# CAN-to-CAN.net
KiCad netlist of a schematic drawn in Altium Designer
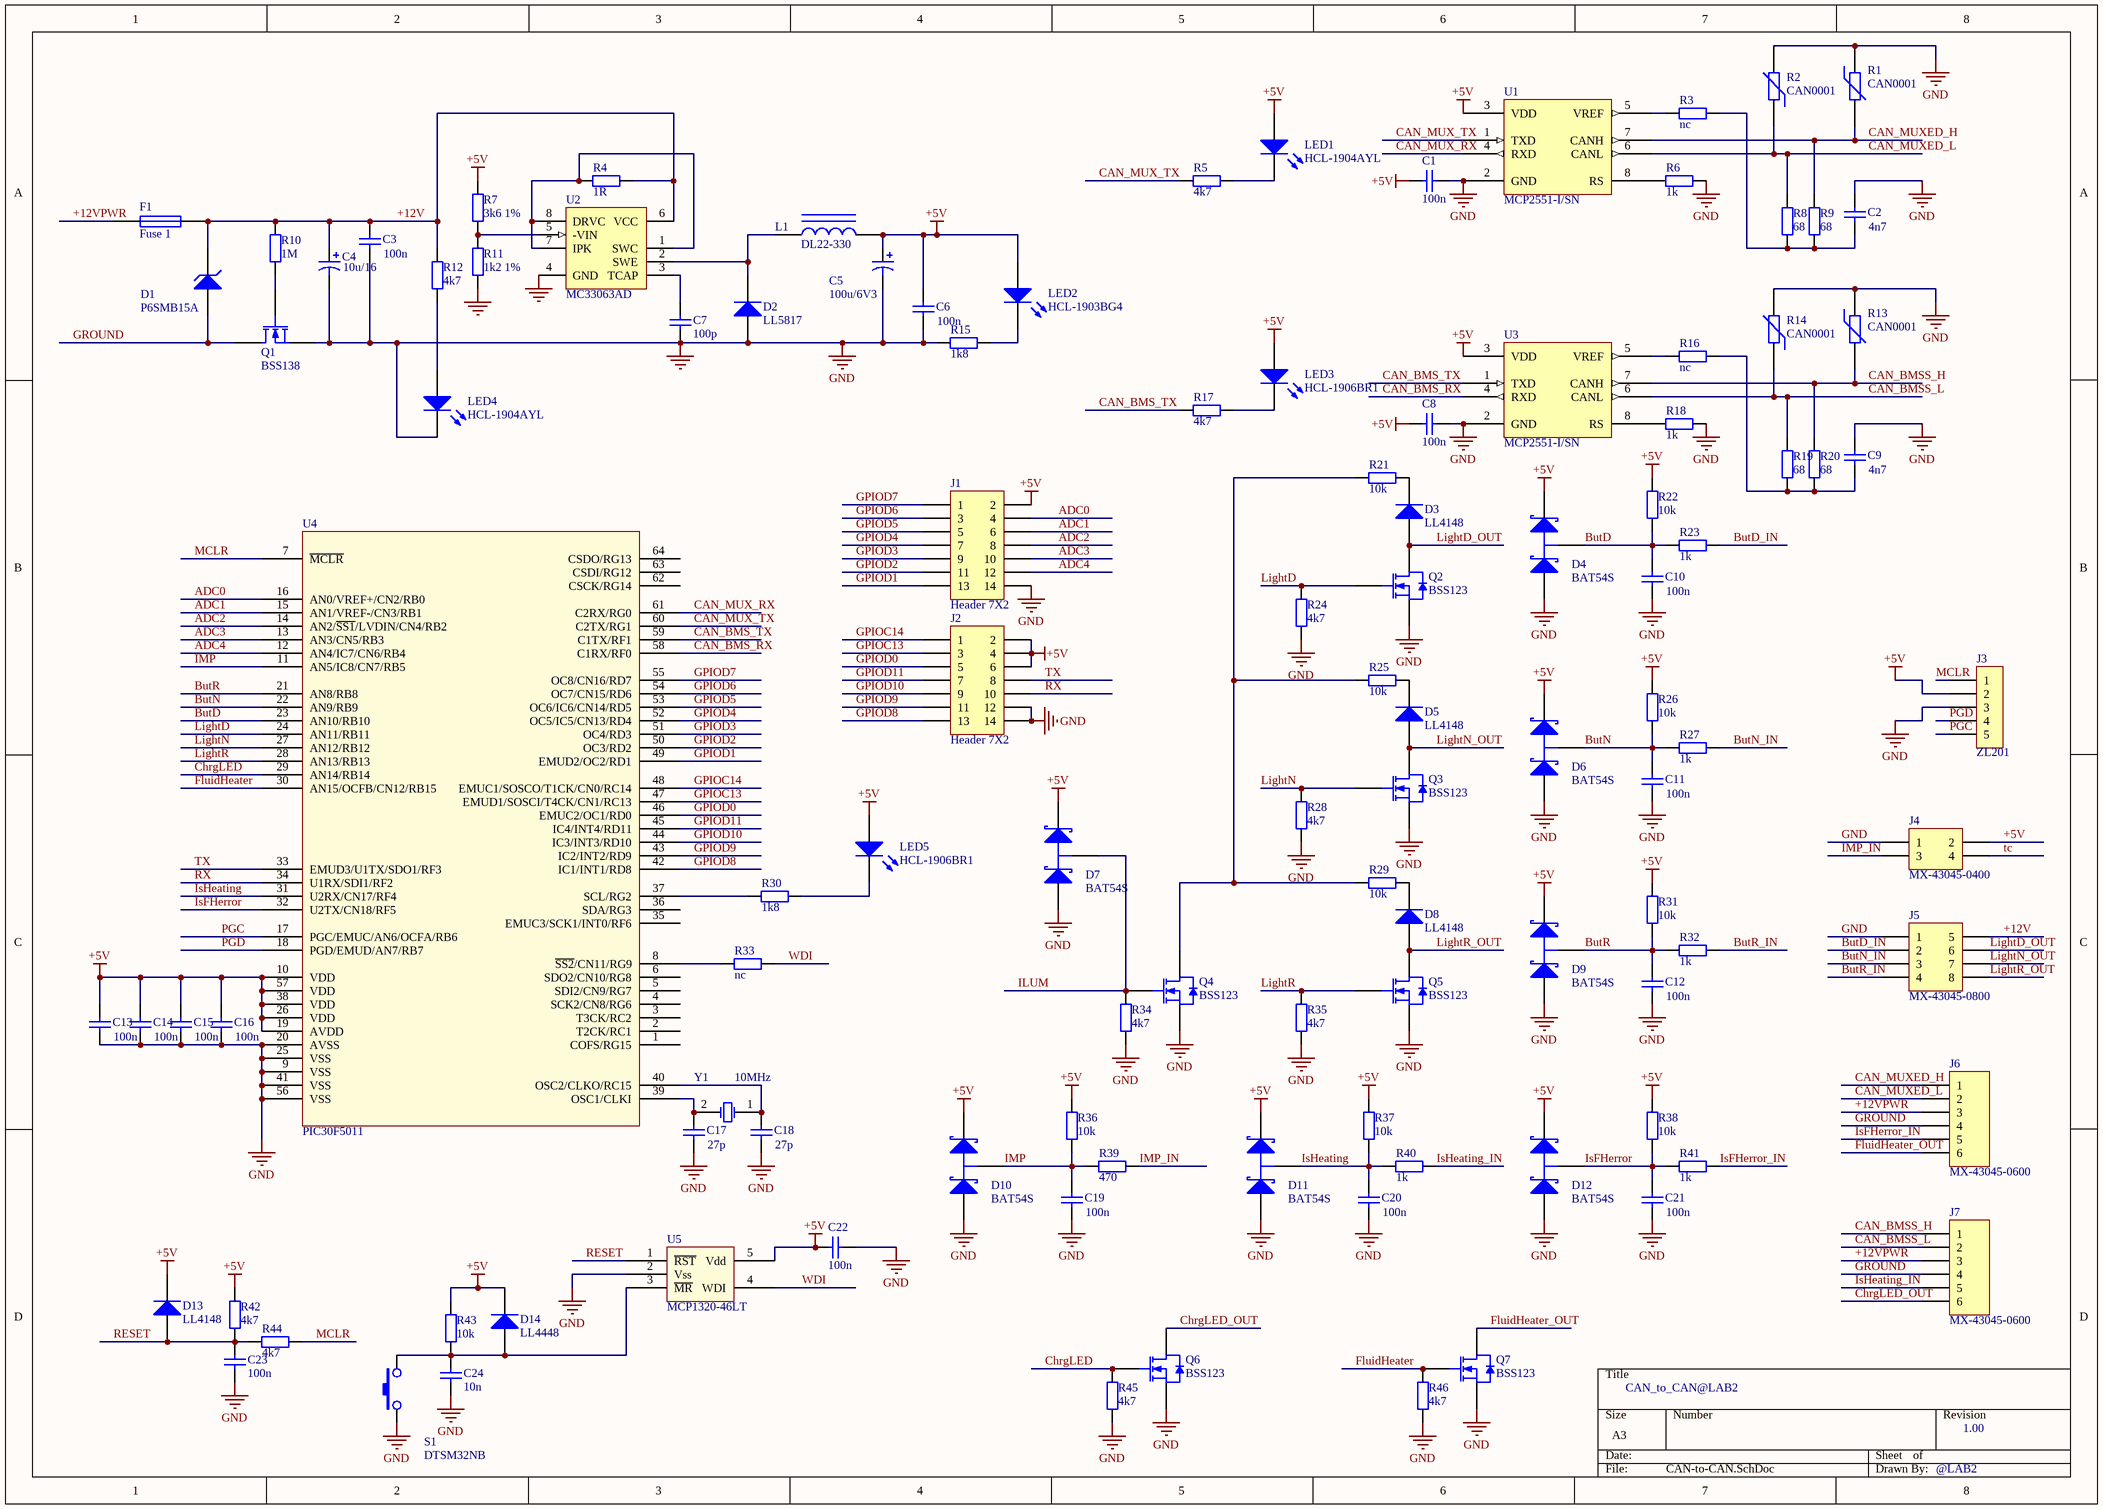
[diagram p0: CAN-to-CAN.SchDoc]

(export (version "E")
  (design (tool "Eeschema 10.0.6"))
  (components
    (comp (ref "C1")
      (value "100n")
      (footprint "0603")
      (description "Capacitor")
      (libsource (lib "Miscellaneous Devices") (part "Cap"))
    )
    (comp (ref "C2")
      (value "4n7")
      (footprint "0603")
      (description "Capacitor")
      (libsource (lib "Miscellaneous Devices") (part "Cap"))
    )
    (comp (ref "C3")
      (value "100n")
      (footprint "3.2X1.6X1.1")
      (description "Capacitor")
      (libsource (lib "Miscellaneous Devices") (part "Cap"))
    )
    (comp (ref "C4")
      (value "10u/16")
      (footprint "1608[0603]")
      (description "Polarized Capacitor (Radial)")
      (libsource (lib "Miscellaneous Devices") (part "Cap Pol1"))
    )
    (comp (ref "C5")
      (value "100u/6V3")
      (footprint "0402")
      (description "Polarized Capacitor (Radial)")
      (libsource (lib "Miscellaneous Devices") (part "Cap Pol1"))
    )
    (comp (ref "C6")
      (value "100n")
      (footprint "0603")
      (description "Capacitor")
      (libsource (lib "Miscellaneous Devices") (part "Cap"))
    )
    (comp (ref "C7")
      (value "100p")
      (footprint "0603")
      (description "Capacitor")
      (libsource (lib "Miscellaneous Devices") (part "Cap"))
    )
    (comp (ref "C8")
      (value "100n")
      (footprint "0603")
      (description "Capacitor")
      (libsource (lib "Miscellaneous Devices") (part "Cap"))
    )
    (comp (ref "C9")
      (value "4n7")
      (footprint "0603")
      (description "Capacitor")
      (libsource (lib "Miscellaneous Devices") (part "Cap"))
    )
    (comp (ref "C10")
      (value "100n")
      (footprint "0603")
      (description "Capacitor")
      (libsource (lib "Miscellaneous Devices") (part "Cap"))
    )
    (comp (ref "C11")
      (value "100n")
      (footprint "0603")
      (description "Capacitor")
      (libsource (lib "Miscellaneous Devices") (part "Cap"))
    )
    (comp (ref "C12")
      (value "100n")
      (footprint "0603")
      (description "Capacitor")
      (libsource (lib "Miscellaneous Devices") (part "Cap"))
    )
    (comp (ref "C13")
      (value "100n")
      (footprint "0603")
      (description "Capacitor")
      (libsource (lib "Miscellaneous Devices") (part "Cap"))
    )
    (comp (ref "C14")
      (value "100n")
      (footprint "0603")
      (description "Capacitor")
      (libsource (lib "Miscellaneous Devices") (part "Cap"))
    )
    (comp (ref "C15")
      (value "100n")
      (footprint "0603")
      (description "Capacitor")
      (libsource (lib "Miscellaneous Devices") (part "Cap"))
    )
    (comp (ref "C16")
      (value "100n")
      (footprint "0603")
      (description "Capacitor")
      (libsource (lib "Miscellaneous Devices") (part "Cap"))
    )
    (comp (ref "C17")
      (value "27p")
      (footprint "0603")
      (description "Capacitor")
      (libsource (lib "Miscellaneous Devices") (part "Cap"))
    )
    (comp (ref "C18")
      (value "27p")
      (footprint "0603")
      (description "Capacitor")
      (libsource (lib "Miscellaneous Devices") (part "Cap"))
    )
    (comp (ref "C19")
      (value "100n")
      (footprint "0603")
      (description "Capacitor")
      (libsource (lib "Miscellaneous Devices") (part "Cap"))
    )
    (comp (ref "C20")
      (value "100n")
      (footprint "0603")
      (description "Capacitor")
      (libsource (lib "Miscellaneous Devices") (part "Cap"))
    )
    (comp (ref "C21")
      (value "100n")
      (footprint "0603")
      (description "Capacitor")
      (libsource (lib "Miscellaneous Devices") (part "Cap"))
    )
    (comp (ref "C22")
      (value "100n")
      (footprint "0603")
      (description "Capacitor")
      (libsource (lib "Miscellaneous Devices") (part "Cap"))
    )
    (comp (ref "C23")
      (value "100n")
      (footprint "0603")
      (description "Capacitor")
      (libsource (lib "Miscellaneous Devices") (part "Cap"))
    )
    (comp (ref "C24")
      (value "10n")
      (footprint "0603")
      (description "Capacitor")
      (libsource (lib "Miscellaneous Devices") (part "Cap"))
    )
    (comp (ref "D1")
      (value "P6SMB15A")
      (footprint "SMB")
      (description "Zener Diode")
      (libsource (lib "Miscellaneous Devices") (part "D Zener"))
    )
    (comp (ref "D2")
      (value "LL5817")
      (footprint "3.2X1.6X1.1")
      (description "High Conductance Fast Diode")
      (libsource (lib "FSC Discrete Diode") (part "1N4148"))
    )
    (comp (ref "D3")
      (value "LL4148")
      (footprint "3.2X1.6X1.1")
      (description "High Conductance Fast Diode")
      (libsource (lib "FSC Discrete Diode") (part "1N4148"))
    )
    (comp (ref "D4")
      (value "BAT54S")
      (footprint "3.2X1.6X1.1")
      (description "Schottky Barrier Double Diode")
      (libsource (lib "Philips Discrete Diode - Schottky") (part "BAT54S"))
    )
    (comp (ref "D5")
      (value "LL4148")
      (footprint "3.2X1.6X1.1")
      (description "High Conductance Fast Diode")
      (libsource (lib "FSC Discrete Diode") (part "1N4148"))
    )
    (comp (ref "D6")
      (value "BAT54S")
      (footprint "3.5X2.8X1.9")
      (description "Schottky Barrier Double Diode")
      (libsource (lib "Philips Discrete Diode - Schottky") (part "BAT54S"))
    )
    (comp (ref "D7")
      (value "BAT54S")
      (footprint "3.2X1.6X1.1")
      (description "Schottky Barrier Double Diode")
      (libsource (lib "Philips Discrete Diode - Schottky") (part "BAT54S"))
    )
    (comp (ref "D8")
      (value "LL4148")
      (footprint "3.2X1.6X1.1")
      (description "High Conductance Fast Diode")
      (libsource (lib "FSC Discrete Diode") (part "1N4148"))
    )
    (comp (ref "D9")
      (value "BAT54S")
      (footprint "3.5X2.8X1.9")
      (description "Schottky Barrier Double Diode")
      (libsource (lib "Philips Discrete Diode - Schottky") (part "BAT54S"))
    )
    (comp (ref "D10")
      (value "BAT54S")
      (footprint "3.2X1.6X1.1")
      (description "Schottky Barrier Double Diode")
      (libsource (lib "Philips Discrete Diode - Schottky") (part "BAT54S"))
    )
    (comp (ref "D11")
      (value "BAT54S")
      (footprint "3.2X1.6X1.1")
      (description "Schottky Barrier Double Diode")
      (libsource (lib "Philips Discrete Diode - Schottky") (part "BAT54S"))
    )
    (comp (ref "D12")
      (value "BAT54S")
      (footprint "3.2X1.6X1.1")
      (description "Schottky Barrier Double Diode")
      (libsource (lib "Philips Discrete Diode - Schottky") (part "BAT54S"))
    )
    (comp (ref "D13")
      (value "LL4148")
      (footprint "3.2X1.6X1.1")
      (description "High Conductance Fast Diode")
      (libsource (lib "FSC Discrete Diode") (part "1N4148"))
    )
    (comp (ref "D14")
      (value "LL4448")
      (footprint "3.2X1.6X1.1")
      (description "Default Diode")
      (libsource (lib "Miscellaneous Devices") (part "Diode"))
    )
    (comp (ref "F1")
      (value "Fuse 1")
      (footprint "1812")
      (description "Fuse")
      (libsource (lib "Miscellaneous Devices") (part "Fuse 1"))
    )
    (comp (ref "J1")
      (value "Header 7X2")
      (footprint "HDR2X7")
      (description "Header, 7-Pin, Dual row")
      (libsource (lib "Miscellaneous Connectors") (part "Header 7X2"))
    )
    (comp (ref "J2")
      (value "Header 7X2")
      (footprint "HDR2X7")
      (description "Header, 7-Pin, Dual row")
      (libsource (lib "Miscellaneous Connectors") (part "Header 7X2"))
    )
    (comp (ref "J3")
      (value "ZL201")
      (footprint "HDR1X5")
      (description "Connector")
      (libsource (lib "*") (part "CON5"))
    )
    (comp (ref "J4")
      (value "MX-43045-0400")
      (footprint "MHDR2X2")
      (description "Header, 2-Pin, Dual row")
      (libsource (lib "Miscellaneous Connectors") (part "Header 2X2"))
    )
    (comp (ref "J5")
      (value "MX-43045-0800")
      (footprint "MHDR2X8")
      (description "Header, 4-Pin, Dual row")
      (libsource (lib "Miscellaneous Connectors") (part "Header 4X2A"))
    )
    (comp (ref "J6")
      (value "MX-43045-0600")
      (footprint "MHDR1X6")
      (description "Header, 6-Pin")
      (libsource (lib "Miscellaneous Connectors") (part "Header 6"))
    )
    (comp (ref "J7")
      (value "MX-43045-0600")
      (footprint "MHDR1X6")
      (description "Header, 6-Pin")
      (libsource (lib "Miscellaneous Connectors") (part "Header 6"))
    )
    (comp (ref "L1")
      (value "DL22-330")
      (footprint "14-1210")
      (description "Magnetic-Core Inductor")
      (libsource (lib "Miscellaneous Devices") (part "Inductor Iron"))
    )
    (comp (ref "LED1")
      (value "HCL-1904AYL")
      (footprint "0603")
      (description "Typical BLUE SiC LED")
      (libsource (lib "Miscellaneous Devices") (part "LED3"))
    )
    (comp (ref "LED2")
      (value "HCL-1903BG4")
      (footprint "0603")
      (description "Typical BLUE SiC LED")
      (libsource (lib "Miscellaneous Devices") (part "LED3"))
    )
    (comp (ref "LED3")
      (value "HCL-1906BR1")
      (footprint "0603")
      (description "Typical BLUE SiC LED")
      (libsource (lib "Miscellaneous Devices") (part "LED3"))
    )
    (comp (ref "LED4")
      (value "HCL-1904AYL")
      (footprint "0603")
      (description "Typical BLUE SiC LED")
      (libsource (lib "Miscellaneous Devices") (part "LED3"))
    )
    (comp (ref "LED5")
      (value "HCL-1906BR1")
      (footprint "0603")
      (description "Typical BLUE SiC LED")
      (libsource (lib "Miscellaneous Devices") (part "LED3"))
    )
    (comp (ref "Q1")
      (value "BSS138")
      (footprint "3.2X1.6X1.1")
      (description "N-Channel Enhancement Mode Vertical DMOS FET")
      (libsource (lib "Zetex Discrete MOSFET") (part "BSS138"))
    )
    (comp (ref "Q2")
      (value "BSS123")
      (footprint "3.2X1.6X1.1")
      (description "N-channel Enhancement Mode Vertical D-MOSFET")
      (libsource (lib "Philips Discrete MOSFET - Low Power") (part "BSS123"))
    )
    (comp (ref "Q3")
      (value "BSS123")
      (footprint "3.2X1.6X1.1")
      (description "N-channel Enhancement Mode Vertical D-MOSFET")
      (libsource (lib "Philips Discrete MOSFET - Low Power") (part "BSS123"))
    )
    (comp (ref "Q4")
      (value "BSS123")
      (footprint "3.5X2.8X1.9")
      (description "N-channel Enhancement Mode Vertical D-MOSFET")
      (libsource (lib "Philips Discrete MOSFET - Low Power") (part "BSS123"))
    )
    (comp (ref "Q5")
      (value "BSS123")
      (footprint "3.5X2.8X1.9")
      (description "N-channel Enhancement Mode Vertical D-MOSFET")
      (libsource (lib "Philips Discrete MOSFET - Low Power") (part "BSS123"))
    )
    (comp (ref "Q6")
      (value "BSS123")
      (footprint "3.2X1.6X1.1")
      (description "N-channel Enhancement Mode Vertical D-MOSFET")
      (libsource (lib "Philips Discrete MOSFET - Low Power") (part "BSS123"))
    )
    (comp (ref "Q7")
      (value "BSS123")
      (footprint "3.5X2.8X1.9")
      (description "N-channel Enhancement Mode Vertical D-MOSFET")
      (libsource (lib "Philips Discrete MOSFET - Low Power") (part "BSS123"))
    )
    (comp (ref "R1")
      (value "CAN0001")
      (footprint "0603")
      (description "Varistor (Voltage-Sensitive Resistor)")
      (libsource (lib "Miscellaneous Devices") (part "Res Varistor"))
    )
    (comp (ref "R2")
      (value "CAN0001")
      (footprint "0603")
      (description "Varistor (Voltage-Sensitive Resistor)")
      (libsource (lib "Miscellaneous Devices") (part "Res Varistor"))
    )
    (comp (ref "R3")
      (value "nc")
      (footprint "0603")
      (description "Resistor")
      (libsource (lib "") (part "Res2_1"))
    )
    (comp (ref "R4")
      (value "1R")
      (footprint "RESC6332")
      (description "Resistor")
      (libsource (lib "") (part "Res2_1"))
    )
    (comp (ref "R5")
      (value "4k7")
      (footprint "0603")
      (description "Resistor")
      (libsource (lib "") (part "Res2_2"))
    )
    (comp (ref "R6")
      (value "1k")
      (footprint "0603")
      (description "Resistor")
      (libsource (lib "") (part "Res2_1"))
    )
    (comp (ref "R7")
      (value "3k6 1%")
      (footprint "0603")
      (description "Resistor")
      (libsource (lib "Miscellaneous Devices") (part "Res2"))
    )
    (comp (ref "R8")
      (value "68")
      (footprint "0603")
      (description "Resistor")
      (libsource (lib "Miscellaneous Devices") (part "Res2"))
    )
    (comp (ref "R9")
      (value "68")
      (footprint "0603")
      (description "Resistor")
      (libsource (lib "Miscellaneous Devices") (part "Res2"))
    )
    (comp (ref "R10")
      (value "1M")
      (footprint "0603")
      (description "Resistor")
      (libsource (lib "Miscellaneous Devices") (part "Res2"))
    )
    (comp (ref "R11")
      (value "1k2 1%")
      (footprint "0603")
      (description "Resistor")
      (libsource (lib "") (part "Res2_3"))
    )
    (comp (ref "R12")
      (value "4k7")
      (footprint "0603")
      (description "Resistor")
      (libsource (lib "Miscellaneous Devices") (part "Res2"))
    )
    (comp (ref "R13")
      (value "CAN0001")
      (footprint "0603")
      (description "Varistor (Voltage-Sensitive Resistor)")
      (libsource (lib "Miscellaneous Devices") (part "Res Varistor"))
    )
    (comp (ref "R14")
      (value "CAN0001")
      (footprint "0603")
      (description "Varistor (Voltage-Sensitive Resistor)")
      (libsource (lib "Miscellaneous Devices") (part "Res Varistor"))
    )
    (comp (ref "R15")
      (value "1k8")
      (footprint "0603")
      (description "Resistor")
      (libsource (lib "") (part "Res2_2"))
    )
    (comp (ref "R16")
      (value "nc")
      (footprint "0603")
      (description "Resistor")
      (libsource (lib "") (part "Res2_1"))
    )
    (comp (ref "R17")
      (value "4k7")
      (footprint "0603")
      (description "Resistor")
      (libsource (lib "") (part "Res2_2"))
    )
    (comp (ref "R18")
      (value "1k")
      (footprint "0603")
      (description "Resistor")
      (libsource (lib "") (part "Res2_1"))
    )
    (comp (ref "R19")
      (value "68")
      (footprint "0603")
      (description "Resistor")
      (libsource (lib "Miscellaneous Devices") (part "Res2"))
    )
    (comp (ref "R20")
      (value "68")
      (footprint "0603")
      (description "Resistor")
      (libsource (lib "Miscellaneous Devices") (part "Res2"))
    )
    (comp (ref "R21")
      (value "10k")
      (footprint "0603")
      (description "Resistor")
      (libsource (lib "") (part "Res2_1"))
    )
    (comp (ref "R22")
      (value "10k")
      (footprint "0603")
      (description "Resistor")
      (libsource (lib "Miscellaneous Devices") (part "Res2"))
    )
    (comp (ref "R23")
      (value "1k")
      (footprint "0603")
      (description "Resistor")
      (libsource (lib "") (part "Res2_2"))
    )
    (comp (ref "R24")
      (value "4k7")
      (footprint "0603")
      (description "Resistor")
      (libsource (lib "Miscellaneous Devices") (part "Res2"))
    )
    (comp (ref "R25")
      (value "10k")
      (footprint "0603")
      (description "Resistor")
      (libsource (lib "") (part "Res2_1"))
    )
    (comp (ref "R26")
      (value "10k")
      (footprint "0603")
      (description "Resistor")
      (libsource (lib "Miscellaneous Devices") (part "Res2"))
    )
    (comp (ref "R27")
      (value "1k")
      (footprint "0603")
      (description "Resistor")
      (libsource (lib "") (part "Res2_2"))
    )
    (comp (ref "R28")
      (value "4k7")
      (footprint "0603")
      (description "Resistor")
      (libsource (lib "Miscellaneous Devices") (part "Res2"))
    )
    (comp (ref "R29")
      (value "10k")
      (footprint "0603")
      (description "Resistor")
      (libsource (lib "") (part "Res2_1"))
    )
    (comp (ref "R30")
      (value "1k8")
      (footprint "0603")
      (description "Resistor")
      (libsource (lib "") (part "Res2_2"))
    )
    (comp (ref "R31")
      (value "10k")
      (footprint "0603")
      (description "Resistor")
      (libsource (lib "Miscellaneous Devices") (part "Res2"))
    )
    (comp (ref "R32")
      (value "1k")
      (footprint "0603")
      (description "Resistor")
      (libsource (lib "") (part "Res2_2"))
    )
    (comp (ref "R33")
      (value "nc")
      (footprint "0603")
      (description "Resistor")
      (libsource (lib "") (part "Res2_2"))
    )
    (comp (ref "R34")
      (value "4k7")
      (footprint "0603")
      (description "Resistor")
      (libsource (lib "Miscellaneous Devices") (part "Res2"))
    )
    (comp (ref "R35")
      (value "4k7")
      (footprint "0603")
      (description "Resistor")
      (libsource (lib "Miscellaneous Devices") (part "Res2"))
    )
    (comp (ref "R36")
      (value "10k")
      (footprint "0603")
      (description "Resistor")
      (libsource (lib "Miscellaneous Devices") (part "Res2"))
    )
    (comp (ref "R37")
      (value "10k")
      (footprint "0603")
      (description "Resistor")
      (libsource (lib "Miscellaneous Devices") (part "Res2"))
    )
    (comp (ref "R38")
      (value "10k")
      (footprint "0603")
      (description "Resistor")
      (libsource (lib "Miscellaneous Devices") (part "Res2"))
    )
    (comp (ref "R39")
      (value "470")
      (footprint "0603")
      (description "Resistor")
      (libsource (lib "") (part "Res2_2"))
    )
    (comp (ref "R40")
      (value "1k")
      (footprint "0603")
      (description "Resistor")
      (libsource (lib "") (part "Res2_2"))
    )
    (comp (ref "R41")
      (value "1k")
      (footprint "0603")
      (description "Resistor")
      (libsource (lib "") (part "Res2_2"))
    )
    (comp (ref "R42")
      (value "4k7")
      (footprint "0603")
      (description "Resistor")
      (libsource (lib "Miscellaneous Devices") (part "Res2"))
    )
    (comp (ref "R43")
      (value "10k")
      (footprint "0603")
      (description "Resistor")
      (libsource (lib "") (part "Res2_3"))
    )
    (comp (ref "R44")
      (value "4k7")
      (footprint "0603")
      (description "Resistor")
      (libsource (lib "") (part "Res2_2"))
    )
    (comp (ref "R45")
      (value "4k7")
      (footprint "0603")
      (description "Resistor")
      (libsource (lib "Miscellaneous Devices") (part "Res2"))
    )
    (comp (ref "R46")
      (value "4k7")
      (footprint "0603")
      (description "Resistor")
      (libsource (lib "Miscellaneous Devices") (part "Res2"))
    )
    (comp (ref "S1")
      (value "DTSM32NB")
      (footprint "3.5X2.8X1.9")
      (description "Switch PushButton")
      (libsource (lib "*") (part "PUSHB"))
    )
    (comp (ref "U1")
      (value "MCP2551-I/SN")
      (footprint "HDR2X8")
      (description "High Speed CAN Transceiver, 8-Pin Plastic SOIC, Industrial Grade")
      (libsource (lib "Microchip Interface Line Transceiver") (part "MCP2551-I/SN"))
    )
    (comp (ref "U2")
      (value "MC33063AD")
      (footprint "SO8_N")
      (description "DC-to-DC Converter Control Circuit")
      (libsource (lib "Motorola Power Mgt DC-DC Converter") (part "MC33063AD"))
    )
    (comp (ref "U3")
      (value "MCP2551-I/SN")
      (footprint "MHDR1X8")
      (description "High Speed CAN Transceiver, 8-Pin Plastic SOIC, Industrial Grade")
      (libsource (lib "Microchip Interface Line Transceiver") (part "MCP2551-I/SN"))
    )
    (comp (ref "U4")
      (value "PIC30F5011")
      (footprint "QFP50P1200X1200X120-64N")
      (description "PIC30F5011 - Up")
      (libsource (lib "X-Tro's Misc") (part "PIC30F5011"))
    )
    (comp (ref "U5")
      (value "MCP1320-46LT")
      (footprint "HDR1X5")
      (libsource (lib "X-Tro's Misc") (part "MCP1320"))
    )
    (comp (ref "Y1")
      (value "10MHz")
      (footprint "3.2X1.6X1.1")
      (description "Crystal Oscillator")
      (libsource (lib "Miscellaneous Devices") (part "XTAL"))
    )
  )
  (nets
    (net (code "1") (name "+5V") (class "Default")
      (node (ref "C1") (pin "1") (pinfunction "1_1") (pintype "passive"))
      (node (ref "C13") (pin "1") (pinfunction "1_1") (pintype "passive"))
      (node (ref "C14") (pin "1") (pinfunction "1_1") (pintype "passive"))
      (node (ref "C15") (pin "1") (pinfunction "1_1") (pintype "passive"))
      (node (ref "C16") (pin "1") (pinfunction "1_1") (pintype "passive"))
      (node (ref "C22") (pin "1") (pinfunction "1_1") (pintype "passive"))
      (node (ref "C5") (pin "1") (pinfunction "1_1") (pintype "passive"))
      (node (ref "C6") (pin "1") (pinfunction "1_1") (pintype "passive"))
      (node (ref "C8") (pin "1") (pinfunction "1_1") (pintype "passive"))
      (node (ref "D10") (pin "2") (pinfunction "K_2") (pintype "passive"))
      (node (ref "D11") (pin "2") (pinfunction "K_2") (pintype "passive"))
      (node (ref "D12") (pin "2") (pinfunction "K_2") (pintype "passive"))
      (node (ref "D13") (pin "2") (pinfunction "K_2") (pintype "passive"))
      (node (ref "D14") (pin "2") (pinfunction "K_2") (pintype "passive"))
      (node (ref "D4") (pin "2") (pinfunction "K_2") (pintype "passive"))
      (node (ref "D6") (pin "2") (pinfunction "K_2") (pintype "passive"))
      (node (ref "D7") (pin "2") (pinfunction "K_2") (pintype "passive"))
      (node (ref "D9") (pin "2") (pinfunction "K_2") (pintype "passive"))
      (node (ref "J1") (pin "2") (pinfunction "2_2") (pintype "passive"))
      (node (ref "J2") (pin "2") (pinfunction "2_2") (pintype "passive"))
      (node (ref "J2") (pin "4") (pinfunction "4_4") (pintype "passive"))
      (node (ref "J2") (pin "6") (pinfunction "6_6") (pintype "passive"))
      (node (ref "J3") (pin "2") (pinfunction "2_2") (pintype "passive"))
      (node (ref "J4") (pin "2") (pinfunction "2_2") (pintype "passive"))
      (node (ref "L1") (pin "2") (pinfunction "2_2") (pintype "passive"))
      (node (ref "LED1") (pin "1") (pinfunction "A_1") (pintype "passive"))
      (node (ref "LED2") (pin "1") (pinfunction "A_1") (pintype "passive"))
      (node (ref "LED3") (pin "1") (pinfunction "A_1") (pintype "passive"))
      (node (ref "LED5") (pin "1") (pinfunction "A_1") (pintype "passive"))
      (node (ref "R22") (pin "1") (pinfunction "1_1") (pintype "passive"))
      (node (ref "R26") (pin "1") (pinfunction "1_1") (pintype "passive"))
      (node (ref "R31") (pin "1") (pinfunction "1_1") (pintype "passive"))
      (node (ref "R36") (pin "1") (pinfunction "1_1") (pintype "passive"))
      (node (ref "R37") (pin "1") (pinfunction "1_1") (pintype "passive"))
      (node (ref "R38") (pin "1") (pinfunction "1_1") (pintype "passive"))
      (node (ref "R42") (pin "1") (pinfunction "1_1") (pintype "passive"))
      (node (ref "R43") (pin "2") (pinfunction "2_2") (pintype "passive"))
      (node (ref "R7") (pin "1") (pinfunction "1_1") (pintype "passive"))
      (node (ref "U1") (pin "3") (pinfunction "VDD_3") (pintype "power_in"))
      (node (ref "U3") (pin "3") (pinfunction "VDD_3") (pintype "power_in"))
      (node (ref "U4") (pin "10") (pinfunction "VDD_10") (pintype "passive"))
      (node (ref "U4") (pin "19") (pinfunction "AVDD_19") (pintype "passive"))
      (node (ref "U4") (pin "26") (pinfunction "VDD_26") (pintype "passive"))
      (node (ref "U4") (pin "38") (pinfunction "VDD_38") (pintype "passive"))
      (node (ref "U4") (pin "57") (pinfunction "VDD_57") (pintype "passive"))
      (node (ref "U5") (pin "5") (pinfunction "Vdd_5") (pintype "passive"))
    )
    (net (code "2") (name "/+12V") (class "Default")
      (node (ref "C3") (pin "1") (pinfunction "1_1") (pintype "passive"))
      (node (ref "C4") (pin "1") (pinfunction "1_1") (pintype "passive"))
      (node (ref "D1") (pin "2") (pinfunction "K_2") (pintype "passive"))
      (node (ref "F1") (pin "2") (pinfunction "2_2") (pintype "passive"))
      (node (ref "J5") (pin "5") (pinfunction "5_5") (pintype "passive"))
      (node (ref "R10") (pin "1") (pinfunction "1_1") (pintype "passive"))
      (node (ref "R12") (pin "1") (pinfunction "1_1") (pintype "passive"))
      (node (ref "R4") (pin "2") (pinfunction "2_2") (pintype "passive"))
      (node (ref "U2") (pin "6") (pinfunction "VCC_6") (pintype "power_in"))
    )
    (net (code "3") (name "/+12VPWR") (class "Default")
      (node (ref "F1") (pin "1") (pinfunction "1_1") (pintype "passive"))
      (node (ref "J6") (pin "3") (pinfunction "3_3") (pintype "passive"))
      (node (ref "J7") (pin "3") (pinfunction "3_3") (pintype "passive"))
    )
    (net (code "4") (name "/ADC0") (class "Default")
      (node (ref "J1") (pin "4") (pinfunction "4_4") (pintype "passive"))
      (node (ref "U4") (pin "16") (pinfunction "AN0/VREF+/CN2/RB0_16") (pintype "passive"))
    )
    (net (code "5") (name "/ADC1") (class "Default")
      (node (ref "J1") (pin "6") (pinfunction "6_6") (pintype "passive"))
      (node (ref "U4") (pin "15") (pinfunction "AN1/VREF-/CN3/RB1_15") (pintype "passive"))
    )
    (net (code "6") (name "/ADC2") (class "Default")
      (node (ref "J1") (pin "8") (pinfunction "8_8") (pintype "passive"))
      (node (ref "U4") (pin "14") (pinfunction "AN2/~{SS1}/LVDIN/CN4/RB2_14") (pintype "passive"))
    )
    (net (code "7") (name "/ADC3") (class "Default")
      (node (ref "J1") (pin "10") (pinfunction "10_10") (pintype "passive"))
      (node (ref "U4") (pin "13") (pinfunction "AN3/CN5/RB3_13") (pintype "passive"))
    )
    (net (code "8") (name "/ADC4") (class "Default")
      (node (ref "J1") (pin "12") (pinfunction "12_12") (pintype "passive"))
      (node (ref "U4") (pin "12") (pinfunction "AN4/IC7/CN6/RB4_12") (pintype "passive"))
    )
    (net (code "9") (name "/ButD") (class "Default")
      (node (ref "C10") (pin "1") (pinfunction "1_1") (pintype "passive"))
      (node (ref "D4") (pin "3") (pinfunction "C_3") (pintype "passive"))
      (node (ref "R22") (pin "2") (pinfunction "2_2") (pintype "passive"))
      (node (ref "R23") (pin "2") (pinfunction "2_2") (pintype "passive"))
      (node (ref "U4") (pin "23") (pinfunction "AN10/RB10_23") (pintype "passive"))
    )
    (net (code "10") (name "/ButD_IN") (class "Default")
      (node (ref "J5") (pin "2") (pinfunction "2_2") (pintype "passive"))
      (node (ref "R23") (pin "1") (pinfunction "1_1") (pintype "passive"))
    )
    (net (code "11") (name "/ButN") (class "Default")
      (node (ref "C11") (pin "1") (pinfunction "1_1") (pintype "passive"))
      (node (ref "D6") (pin "3") (pinfunction "C_3") (pintype "passive"))
      (node (ref "R26") (pin "2") (pinfunction "2_2") (pintype "passive"))
      (node (ref "R27") (pin "2") (pinfunction "2_2") (pintype "passive"))
      (node (ref "U4") (pin "22") (pinfunction "AN9/RB9_22") (pintype "passive"))
    )
    (net (code "12") (name "/ButN_IN") (class "Default")
      (node (ref "J5") (pin "3") (pinfunction "3_3") (pintype "passive"))
      (node (ref "R27") (pin "1") (pinfunction "1_1") (pintype "passive"))
    )
    (net (code "13") (name "/ButR") (class "Default")
      (node (ref "C12") (pin "1") (pinfunction "1_1") (pintype "passive"))
      (node (ref "D9") (pin "3") (pinfunction "C_3") (pintype "passive"))
      (node (ref "R31") (pin "2") (pinfunction "2_2") (pintype "passive"))
      (node (ref "R32") (pin "2") (pinfunction "2_2") (pintype "passive"))
      (node (ref "U4") (pin "21") (pinfunction "AN8/RB8_21") (pintype "passive"))
    )
    (net (code "14") (name "/ButR_IN") (class "Default")
      (node (ref "J5") (pin "4") (pinfunction "4_4") (pintype "passive"))
      (node (ref "R32") (pin "1") (pinfunction "1_1") (pintype "passive"))
    )
    (net (code "15") (name "/CAN_BMSS_H") (class "Default")
      (node (ref "J7") (pin "1") (pinfunction "1_1") (pintype "passive"))
      (node (ref "R13") (pin "2") (pinfunction "2_2") (pintype "passive"))
      (node (ref "R20") (pin "1") (pinfunction "1_1") (pintype "passive"))
      (node (ref "U3") (pin "7") (pinfunction "CANH_7") (pintype "output"))
    )
    (net (code "16") (name "/CAN_BMSS_L") (class "Default")
      (node (ref "J7") (pin "2") (pinfunction "2_2") (pintype "passive"))
      (node (ref "R14") (pin "1") (pinfunction "1_1") (pintype "passive"))
      (node (ref "R19") (pin "1") (pinfunction "1_1") (pintype "passive"))
      (node (ref "U3") (pin "6") (pinfunction "CANL_6") (pintype "output"))
    )
    (net (code "17") (name "/CAN_BMS_RX") (class "Default")
      (node (ref "U3") (pin "4") (pinfunction "RXD_4") (pintype "output"))
      (node (ref "U4") (pin "58") (pinfunction "C1RX/RF0_58") (pintype "passive"))
    )
    (net (code "18") (name "/CAN_BMS_TX") (class "Default")
      (node (ref "R17") (pin "2") (pinfunction "2_2") (pintype "passive"))
      (node (ref "U3") (pin "1") (pinfunction "TXD_1") (pintype "input"))
      (node (ref "U4") (pin "59") (pinfunction "C1TX/RF1_59") (pintype "passive"))
    )
    (net (code "19") (name "/CAN_MUXED_H") (class "Default")
      (node (ref "J6") (pin "1") (pinfunction "1_1") (pintype "passive"))
      (node (ref "R1") (pin "2") (pinfunction "2_2") (pintype "passive"))
      (node (ref "R9") (pin "1") (pinfunction "1_1") (pintype "passive"))
      (node (ref "U1") (pin "7") (pinfunction "CANH_7") (pintype "output"))
    )
    (net (code "20") (name "/CAN_MUXED_L") (class "Default")
      (node (ref "J6") (pin "2") (pinfunction "2_2") (pintype "passive"))
      (node (ref "R2") (pin "1") (pinfunction "1_1") (pintype "passive"))
      (node (ref "R8") (pin "1") (pinfunction "1_1") (pintype "passive"))
      (node (ref "U1") (pin "6") (pinfunction "CANL_6") (pintype "output"))
    )
    (net (code "21") (name "/CAN_MUX_RX") (class "Default")
      (node (ref "U1") (pin "4") (pinfunction "RXD_4") (pintype "output"))
      (node (ref "U4") (pin "61") (pinfunction "C2RX/RG0_61") (pintype "passive"))
    )
    (net (code "22") (name "/CAN_MUX_TX") (class "Default")
      (node (ref "R5") (pin "2") (pinfunction "2_2") (pintype "passive"))
      (node (ref "U1") (pin "1") (pinfunction "TXD_1") (pintype "input"))
      (node (ref "U4") (pin "60") (pinfunction "C2TX/RG1_60") (pintype "passive"))
    )
    (net (code "23") (name "/ChrgLED") (class "Default")
      (node (ref "Q6") (pin "3") (pinfunction "G_3") (pintype "passive"))
      (node (ref "R45") (pin "1") (pinfunction "1_1") (pintype "passive"))
      (node (ref "U4") (pin "29") (pinfunction "AN14/RB14_29") (pintype "passive"))
    )
    (net (code "24") (name "/ChrgLED_OUT") (class "Default")
      (node (ref "J7") (pin "6") (pinfunction "6_6") (pintype "passive"))
      (node (ref "Q6") (pin "1") (pinfunction "D_1") (pintype "passive"))
    )
    (net (code "25") (name "/FluidHeater") (class "Default")
      (node (ref "Q7") (pin "3") (pinfunction "G_3") (pintype "passive"))
      (node (ref "R46") (pin "1") (pinfunction "1_1") (pintype "passive"))
      (node (ref "U4") (pin "30") (pinfunction "AN15/OCFB/CN12/RB15_30") (pintype "passive"))
    )
    (net (code "26") (name "/FluidHeater_OUT") (class "Default")
      (node (ref "J6") (pin "6") (pinfunction "6_6") (pintype "passive"))
      (node (ref "Q7") (pin "1") (pinfunction "D_1") (pintype "passive"))
    )
    (net (code "27") (name "/GPIOC13") (class "Default")
      (node (ref "J2") (pin "3") (pinfunction "3_3") (pintype "passive"))
      (node (ref "U4") (pin "47") (pinfunction "EMUD1/SOSCI/T4CK/CN1/RC13_47") (pintype "passive"))
    )
    (net (code "28") (name "/GPIOC14") (class "Default")
      (node (ref "J2") (pin "1") (pinfunction "1_1") (pintype "passive"))
      (node (ref "U4") (pin "48") (pinfunction "EMUC1/SOSCO/T1CK/CN0/RC14_48") (pintype "passive"))
    )
    (net (code "29") (name "/GPIOD0") (class "Default")
      (node (ref "J2") (pin "5") (pinfunction "5_5") (pintype "passive"))
      (node (ref "U4") (pin "46") (pinfunction "EMUC2/OC1/RD0_46") (pintype "passive"))
    )
    (net (code "30") (name "/GPIOD1") (class "Default")
      (node (ref "J1") (pin "13") (pinfunction "13_13") (pintype "passive"))
      (node (ref "U4") (pin "49") (pinfunction "EMUD2/OC2/RD1_49") (pintype "passive"))
    )
    (net (code "31") (name "/GPIOD2") (class "Default")
      (node (ref "J1") (pin "11") (pinfunction "11_11") (pintype "passive"))
      (node (ref "U4") (pin "50") (pinfunction "OC3/RD2_50") (pintype "passive"))
    )
    (net (code "32") (name "/GPIOD3") (class "Default")
      (node (ref "J1") (pin "9") (pinfunction "9_9") (pintype "passive"))
      (node (ref "U4") (pin "51") (pinfunction "OC4/RD3_51") (pintype "passive"))
    )
    (net (code "33") (name "/GPIOD4") (class "Default")
      (node (ref "J1") (pin "7") (pinfunction "7_7") (pintype "passive"))
      (node (ref "U4") (pin "52") (pinfunction "OC5/IC5/CN13/RD4_52") (pintype "passive"))
    )
    (net (code "34") (name "/GPIOD5") (class "Default")
      (node (ref "J1") (pin "5") (pinfunction "5_5") (pintype "passive"))
      (node (ref "U4") (pin "53") (pinfunction "OC6/IC6/CN14/RD5_53") (pintype "passive"))
    )
    (net (code "35") (name "/GPIOD6") (class "Default")
      (node (ref "J1") (pin "3") (pinfunction "3_3") (pintype "passive"))
      (node (ref "U4") (pin "54") (pinfunction "OC7/CN15/RD6_54") (pintype "passive"))
    )
    (net (code "36") (name "/GPIOD7") (class "Default")
      (node (ref "J1") (pin "1") (pinfunction "1_1") (pintype "passive"))
      (node (ref "U4") (pin "55") (pinfunction "OC8/CN16/RD7_55") (pintype "passive"))
    )
    (net (code "37") (name "/GPIOD8") (class "Default")
      (node (ref "J2") (pin "13") (pinfunction "13_13") (pintype "passive"))
      (node (ref "U4") (pin "42") (pinfunction "IC1/INT1/RD8_42") (pintype "passive"))
    )
    (net (code "38") (name "/GPIOD9") (class "Default")
      (node (ref "J2") (pin "11") (pinfunction "11_11") (pintype "passive"))
      (node (ref "U4") (pin "43") (pinfunction "IC2/INT2/RD9_43") (pintype "passive"))
    )
    (net (code "39") (name "/GPIOD10") (class "Default")
      (node (ref "J2") (pin "9") (pinfunction "9_9") (pintype "passive"))
      (node (ref "U4") (pin "44") (pinfunction "IC3/INT3/RD10_44") (pintype "passive"))
    )
    (net (code "40") (name "/GPIOD11") (class "Default")
      (node (ref "J2") (pin "7") (pinfunction "7_7") (pintype "passive"))
      (node (ref "U4") (pin "45") (pinfunction "IC4/INT4/RD11_45") (pintype "passive"))
    )
    (net (code "41") (name "/GROUND") (class "Default")
      (node (ref "D1") (pin "1") (pinfunction "A_1") (pintype "passive"))
      (node (ref "J6") (pin "4") (pinfunction "4_4") (pintype "passive"))
      (node (ref "J7") (pin "4") (pinfunction "4_4") (pintype "passive"))
      (node (ref "Q1") (pin "1") (pinfunction "D_1") (pintype "passive"))
    )
    (net (code "42") (name "/ILUM") (class "Default")
      (node (ref "D7") (pin "3") (pinfunction "C_3") (pintype "passive"))
      (node (ref "Q4") (pin "3") (pinfunction "G_3") (pintype "passive"))
      (node (ref "R34") (pin "1") (pinfunction "1_1") (pintype "passive"))
    )
    (net (code "43") (name "/IMP") (class "Default")
      (node (ref "C19") (pin "1") (pinfunction "1_1") (pintype "passive"))
      (node (ref "D10") (pin "3") (pinfunction "C_3") (pintype "passive"))
      (node (ref "R36") (pin "2") (pinfunction "2_2") (pintype "passive"))
      (node (ref "R39") (pin "2") (pinfunction "2_2") (pintype "passive"))
      (node (ref "U4") (pin "11") (pinfunction "AN5/IC8/CN7/RB5_11") (pintype "passive"))
    )
    (net (code "44") (name "/IMP_IN") (class "Default")
      (node (ref "J4") (pin "3") (pinfunction "3_3") (pintype "passive"))
      (node (ref "R39") (pin "1") (pinfunction "1_1") (pintype "passive"))
    )
    (net (code "45") (name "/IsFHerror") (class "Default")
      (node (ref "C21") (pin "1") (pinfunction "1_1") (pintype "passive"))
      (node (ref "D12") (pin "3") (pinfunction "C_3") (pintype "passive"))
      (node (ref "R38") (pin "2") (pinfunction "2_2") (pintype "passive"))
      (node (ref "R41") (pin "2") (pinfunction "2_2") (pintype "passive"))
      (node (ref "U4") (pin "32") (pinfunction "U2TX/CN18/RF5_32") (pintype "passive"))
    )
    (net (code "46") (name "/IsFHerror_IN") (class "Default")
      (node (ref "J6") (pin "5") (pinfunction "5_5") (pintype "passive"))
      (node (ref "R41") (pin "1") (pinfunction "1_1") (pintype "passive"))
    )
    (net (code "47") (name "/IsHeating") (class "Default")
      (node (ref "C20") (pin "1") (pinfunction "1_1") (pintype "passive"))
      (node (ref "D11") (pin "3") (pinfunction "C_3") (pintype "passive"))
      (node (ref "R37") (pin "2") (pinfunction "2_2") (pintype "passive"))
      (node (ref "R40") (pin "2") (pinfunction "2_2") (pintype "passive"))
      (node (ref "U4") (pin "31") (pinfunction "U2RX/CN17/RF4_31") (pintype "passive"))
    )
    (net (code "48") (name "/IsHeating_IN") (class "Default")
      (node (ref "J7") (pin "5") (pinfunction "5_5") (pintype "passive"))
      (node (ref "R40") (pin "1") (pinfunction "1_1") (pintype "passive"))
    )
    (net (code "49") (name "/LightD") (class "Default")
      (node (ref "Q2") (pin "3") (pinfunction "G_3") (pintype "passive"))
      (node (ref "R24") (pin "1") (pinfunction "1_1") (pintype "passive"))
      (node (ref "U4") (pin "24") (pinfunction "AN11/RB11_24") (pintype "passive"))
    )
    (net (code "50") (name "/LightD_OUT") (class "Default")
      (node (ref "D3") (pin "1") (pinfunction "A_1") (pintype "passive"))
      (node (ref "J5") (pin "6") (pinfunction "6_6") (pintype "passive"))
      (node (ref "Q2") (pin "1") (pinfunction "D_1") (pintype "passive"))
    )
    (net (code "51") (name "/LightN") (class "Default")
      (node (ref "Q3") (pin "3") (pinfunction "G_3") (pintype "passive"))
      (node (ref "R28") (pin "1") (pinfunction "1_1") (pintype "passive"))
      (node (ref "U4") (pin "27") (pinfunction "AN12/RB12_27") (pintype "passive"))
    )
    (net (code "52") (name "/LightN_OUT") (class "Default")
      (node (ref "D5") (pin "1") (pinfunction "A_1") (pintype "passive"))
      (node (ref "J5") (pin "7") (pinfunction "7_7") (pintype "passive"))
      (node (ref "Q3") (pin "1") (pinfunction "D_1") (pintype "passive"))
    )
    (net (code "53") (name "/LightR") (class "Default")
      (node (ref "Q5") (pin "3") (pinfunction "G_3") (pintype "passive"))
      (node (ref "R35") (pin "1") (pinfunction "1_1") (pintype "passive"))
      (node (ref "U4") (pin "28") (pinfunction "AN13/RB13_28") (pintype "passive"))
    )
    (net (code "54") (name "/LightR_OUT") (class "Default")
      (node (ref "D8") (pin "1") (pinfunction "A_1") (pintype "passive"))
      (node (ref "J5") (pin "8") (pinfunction "8_8") (pintype "passive"))
      (node (ref "Q5") (pin "1") (pinfunction "D_1") (pintype "passive"))
    )
    (net (code "55") (name "/MCLR") (class "Default")
      (node (ref "J3") (pin "1") (pinfunction "1_1") (pintype "passive"))
      (node (ref "R44") (pin "1") (pinfunction "1_1") (pintype "passive"))
      (node (ref "U4") (pin "7") (pinfunction "~{MCLR}_7") (pintype "passive"))
    )
    (net (code "56") (name "/PGC") (class "Default")
      (node (ref "J3") (pin "5") (pinfunction "5_5") (pintype "passive"))
      (node (ref "U4") (pin "17") (pinfunction "PGC/EMUC/AN6/OCFA/RB6_17") (pintype "passive"))
    )
    (net (code "57") (name "/PGD") (class "Default")
      (node (ref "J3") (pin "4") (pinfunction "4_4") (pintype "passive"))
      (node (ref "U4") (pin "18") (pinfunction "PGD/EMUD/AN7/RB7_18") (pintype "passive"))
    )
    (net (code "58") (name "/RESET") (class "Default")
      (node (ref "C23") (pin "2") (pinfunction "2_2") (pintype "passive"))
      (node (ref "D13") (pin "1") (pinfunction "A_1") (pintype "passive"))
      (node (ref "R42") (pin "2") (pinfunction "2_2") (pintype "passive"))
      (node (ref "R44") (pin "2") (pinfunction "2_2") (pintype "passive"))
      (node (ref "U5") (pin "1") (pinfunction "~{RST}_1") (pintype "passive"))
    )
    (net (code "59") (name "/RX") (class "Default")
      (node (ref "J2") (pin "10") (pinfunction "10_10") (pintype "passive"))
      (node (ref "U4") (pin "34") (pinfunction "U1RX/SDI1/RF2_34") (pintype "passive"))
    )
    (net (code "60") (name "/TX") (class "Default")
      (node (ref "J2") (pin "8") (pinfunction "8_8") (pintype "passive"))
      (node (ref "U4") (pin "33") (pinfunction "EMUD3/U1TX/SDO1/RF3_33") (pintype "passive"))
    )
    (net (code "61") (name "/WDI") (class "Default")
      (node (ref "R33") (pin "1") (pinfunction "1_1") (pintype "passive"))
      (node (ref "U5") (pin "4") (pinfunction "WDI_4") (pintype "passive"))
    )
    (net (code "62") (name "/tc") (class "Default")
      (node (ref "J4") (pin "4") (pinfunction "4_4") (pintype "passive"))
    )
    (net (code "63") (name "GND") (class "Default")
      (node (ref "C1") (pin "2") (pinfunction "2_2") (pintype "passive"))
      (node (ref "C10") (pin "2") (pinfunction "2_2") (pintype "passive"))
      (node (ref "C11") (pin "2") (pinfunction "2_2") (pintype "passive"))
      (node (ref "C12") (pin "2") (pinfunction "2_2") (pintype "passive"))
      (node (ref "C13") (pin "2") (pinfunction "2_2") (pintype "passive"))
      (node (ref "C14") (pin "2") (pinfunction "2_2") (pintype "passive"))
      (node (ref "C15") (pin "2") (pinfunction "2_2") (pintype "passive"))
      (node (ref "C16") (pin "2") (pinfunction "2_2") (pintype "passive"))
      (node (ref "C17") (pin "2") (pinfunction "2_2") (pintype "passive"))
      (node (ref "C18") (pin "2") (pinfunction "2_2") (pintype "passive"))
      (node (ref "C19") (pin "2") (pinfunction "2_2") (pintype "passive"))
      (node (ref "C2") (pin "1") (pinfunction "1_1") (pintype "passive"))
      (node (ref "C20") (pin "2") (pinfunction "2_2") (pintype "passive"))
      (node (ref "C21") (pin "2") (pinfunction "2_2") (pintype "passive"))
      (node (ref "C22") (pin "2") (pinfunction "2_2") (pintype "passive"))
      (node (ref "C23") (pin "1") (pinfunction "1_1") (pintype "passive"))
      (node (ref "C24") (pin "1") (pinfunction "1_1") (pintype "passive"))
      (node (ref "C3") (pin "2") (pinfunction "2_2") (pintype "passive"))
      (node (ref "C4") (pin "2") (pinfunction "2_2") (pintype "passive"))
      (node (ref "C5") (pin "2") (pinfunction "2_2") (pintype "passive"))
      (node (ref "C6") (pin "2") (pinfunction "2_2") (pintype "passive"))
      (node (ref "C7") (pin "1") (pinfunction "1_1") (pintype "passive"))
      (node (ref "C8") (pin "2") (pinfunction "2_2") (pintype "passive"))
      (node (ref "C9") (pin "1") (pinfunction "1_1") (pintype "passive"))
      (node (ref "D10") (pin "1") (pinfunction "A_1") (pintype "passive"))
      (node (ref "D11") (pin "1") (pinfunction "A_1") (pintype "passive"))
      (node (ref "D12") (pin "1") (pinfunction "A_1") (pintype "passive"))
      (node (ref "D2") (pin "1") (pinfunction "A_1") (pintype "passive"))
      (node (ref "D4") (pin "1") (pinfunction "A_1") (pintype "passive"))
      (node (ref "D6") (pin "1") (pinfunction "A_1") (pintype "passive"))
      (node (ref "D7") (pin "1") (pinfunction "A_1") (pintype "passive"))
      (node (ref "D9") (pin "1") (pinfunction "A_1") (pintype "passive"))
      (node (ref "J1") (pin "14") (pinfunction "14_14") (pintype "passive"))
      (node (ref "J2") (pin "12") (pinfunction "12_12") (pintype "passive"))
      (node (ref "J2") (pin "14") (pinfunction "14_14") (pintype "passive"))
      (node (ref "J3") (pin "3") (pinfunction "3_3") (pintype "passive"))
      (node (ref "J4") (pin "1") (pinfunction "1_1") (pintype "passive"))
      (node (ref "J5") (pin "1") (pinfunction "1_1") (pintype "passive"))
      (node (ref "LED4") (pin "2") (pinfunction "K_2") (pintype "passive"))
      (node (ref "Q1") (pin "2") (pinfunction "S_2") (pintype "passive"))
      (node (ref "Q2") (pin "2") (pinfunction "S_2") (pintype "passive"))
      (node (ref "Q3") (pin "2") (pinfunction "S_2") (pintype "passive"))
      (node (ref "Q4") (pin "2") (pinfunction "S_2") (pintype "passive"))
      (node (ref "Q5") (pin "2") (pinfunction "S_2") (pintype "passive"))
      (node (ref "Q6") (pin "2") (pinfunction "S_2") (pintype "passive"))
      (node (ref "Q7") (pin "2") (pinfunction "S_2") (pintype "passive"))
      (node (ref "R1") (pin "1") (pinfunction "1_1") (pintype "passive"))
      (node (ref "R11") (pin "1") (pinfunction "1_1") (pintype "passive"))
      (node (ref "R13") (pin "1") (pinfunction "1_1") (pintype "passive"))
      (node (ref "R14") (pin "2") (pinfunction "2_2") (pintype "passive"))
      (node (ref "R15") (pin "2") (pinfunction "2_2") (pintype "passive"))
      (node (ref "R18") (pin "2") (pinfunction "2_2") (pintype "passive"))
      (node (ref "R2") (pin "2") (pinfunction "2_2") (pintype "passive"))
      (node (ref "R24") (pin "2") (pinfunction "2_2") (pintype "passive"))
      (node (ref "R28") (pin "2") (pinfunction "2_2") (pintype "passive"))
      (node (ref "R34") (pin "2") (pinfunction "2_2") (pintype "passive"))
      (node (ref "R35") (pin "2") (pinfunction "2_2") (pintype "passive"))
      (node (ref "R45") (pin "2") (pinfunction "2_2") (pintype "passive"))
      (node (ref "R46") (pin "2") (pinfunction "2_2") (pintype "passive"))
      (node (ref "R6") (pin "2") (pinfunction "2_2") (pintype "passive"))
      (node (ref "S1") (pin "1") (pintype "passive"))
      (node (ref "U1") (pin "2") (pinfunction "GND_2") (pintype "power_in"))
      (node (ref "U2") (pin "4") (pinfunction "GND_4") (pintype "power_in"))
      (node (ref "U3") (pin "2") (pinfunction "GND_2") (pintype "power_in"))
      (node (ref "U4") (pin "20") (pinfunction "AVSS_20") (pintype "passive"))
      (node (ref "U4") (pin "25") (pinfunction "VSS_25") (pintype "passive"))
      (node (ref "U4") (pin "41") (pinfunction "VSS_41") (pintype "passive"))
      (node (ref "U4") (pin "56") (pinfunction "VSS_56") (pintype "passive"))
      (node (ref "U4") (pin "9") (pinfunction "VSS_9") (pintype "passive"))
      (node (ref "U5") (pin "2") (pinfunction "Vss_2") (pintype "passive"))
    )
    (net (code "64") (name "Net-(C2-Pad2)") (class "Default")
      (node (ref "C2") (pin "2") (pinfunction "2_2") (pintype "passive"))
      (node (ref "R3") (pin "2") (pinfunction "2_2") (pintype "passive"))
      (node (ref "R8") (pin "2") (pinfunction "2_2") (pintype "passive"))
      (node (ref "R9") (pin "2") (pinfunction "2_2") (pintype "passive"))
    )
    (net (code "65") (name "Net-(C9-Pad2)") (class "Default")
      (node (ref "C9") (pin "2") (pinfunction "2_2") (pintype "passive"))
      (node (ref "R16") (pin "2") (pinfunction "2_2") (pintype "passive"))
      (node (ref "R19") (pin "2") (pinfunction "2_2") (pintype "passive"))
      (node (ref "R20") (pin "2") (pinfunction "2_2") (pintype "passive"))
    )
    (net (code "66") (name "Net-(D2-K)") (class "Default")
      (node (ref "D2") (pin "2") (pinfunction "K_2") (pintype "passive"))
      (node (ref "L1") (pin "1") (pinfunction "1_1") (pintype "passive"))
      (node (ref "U2") (pin "2") (pinfunction "SWE_2") (pintype "open_emitter"))
    )
    (net (code "67") (name "Net-(D3-K)") (class "Default")
      (node (ref "D3") (pin "2") (pinfunction "K_2") (pintype "passive"))
      (node (ref "R21") (pin "2") (pinfunction "2_2") (pintype "passive"))
    )
    (net (code "68") (name "Net-(D5-K)") (class "Default")
      (node (ref "D5") (pin "2") (pinfunction "K_2") (pintype "passive"))
      (node (ref "R25") (pin "2") (pinfunction "2_2") (pintype "passive"))
    )
    (net (code "69") (name "Net-(D8-K)") (class "Default")
      (node (ref "D8") (pin "2") (pinfunction "K_2") (pintype "passive"))
      (node (ref "R29") (pin "2") (pinfunction "2_2") (pintype "passive"))
    )
    (net (code "70") (name "Net-(D14-A)") (class "Default")
      (node (ref "C24") (pin "2") (pinfunction "2_2") (pintype "passive"))
      (node (ref "D14") (pin "1") (pinfunction "A_1") (pintype "passive"))
      (node (ref "R43") (pin "1") (pinfunction "1_1") (pintype "passive"))
      (node (ref "S1") (pin "2") (pintype "passive"))
      (node (ref "U5") (pin "3") (pinfunction "~{MR}_3") (pintype "passive"))
    )
    (net (code "71") (name "Net-(LED1-K)") (class "Default")
      (node (ref "LED1") (pin "2") (pinfunction "K_2") (pintype "passive"))
      (node (ref "R5") (pin "1") (pinfunction "1_1") (pintype "passive"))
    )
    (net (code "72") (name "Net-(LED2-K)") (class "Default")
      (node (ref "LED2") (pin "2") (pinfunction "K_2") (pintype "passive"))
      (node (ref "R15") (pin "1") (pinfunction "1_1") (pintype "passive"))
    )
    (net (code "73") (name "Net-(LED3-K)") (class "Default")
      (node (ref "LED3") (pin "2") (pinfunction "K_2") (pintype "passive"))
      (node (ref "R17") (pin "1") (pinfunction "1_1") (pintype "passive"))
    )
    (net (code "74") (name "Net-(LED4-A)") (class "Default")
      (node (ref "LED4") (pin "1") (pinfunction "A_1") (pintype "passive"))
      (node (ref "R12") (pin "2") (pinfunction "2_2") (pintype "passive"))
    )
    (net (code "75") (name "Net-(LED5-K)") (class "Default")
      (node (ref "LED5") (pin "2") (pinfunction "K_2") (pintype "passive"))
      (node (ref "R30") (pin "1") (pinfunction "1_1") (pintype "passive"))
    )
    (net (code "76") (name "Net-(Q1-G)") (class "Default")
      (node (ref "Q1") (pin "3") (pinfunction "G_3") (pintype "passive"))
      (node (ref "R10") (pin "2") (pinfunction "2_2") (pintype "passive"))
    )
    (net (code "77") (name "Net-(Q4-D)") (class "Default")
      (node (ref "Q4") (pin "1") (pinfunction "D_1") (pintype "passive"))
      (node (ref "R21") (pin "1") (pinfunction "1_1") (pintype "passive"))
      (node (ref "R25") (pin "1") (pinfunction "1_1") (pintype "passive"))
      (node (ref "R29") (pin "1") (pinfunction "1_1") (pintype "passive"))
    )
    (net (code "78") (name "Net-(U1-RS)") (class "Default")
      (node (ref "R6") (pin "1") (pinfunction "1_1") (pintype "passive"))
      (node (ref "U1") (pin "8") (pinfunction "RS_8") (pintype "passive"))
    )
    (net (code "79") (name "Net-(U1-VREF)") (class "Default")
      (node (ref "R3") (pin "1") (pinfunction "1_1") (pintype "passive"))
      (node (ref "U1") (pin "5") (pinfunction "VREF_5") (pintype "output"))
    )
    (net (code "80") (name "Net-(U2--VIN)") (class "Default")
      (node (ref "R11") (pin "2") (pinfunction "2_2") (pintype "passive"))
      (node (ref "R7") (pin "2") (pinfunction "2_2") (pintype "passive"))
      (node (ref "U2") (pin "5") (pinfunction "-VIN_5") (pintype "input"))
    )
    (net (code "81") (name "Net-(U2-DRVC)") (class "Default")
      (node (ref "R4") (pin "1") (pinfunction "1_1") (pintype "passive"))
      (node (ref "U2") (pin "1") (pinfunction "SWC_1") (pintype "open_collector"))
      (node (ref "U2") (pin "7") (pinfunction "IPK_7") (pintype "passive"))
      (node (ref "U2") (pin "8") (pinfunction "DRVC_8") (pintype "open_collector"))
    )
    (net (code "82") (name "Net-(U2-TCAP)") (class "Default")
      (node (ref "C7") (pin "2") (pinfunction "2_2") (pintype "passive"))
      (node (ref "U2") (pin "3") (pinfunction "TCAP_3") (pintype "passive"))
    )
    (net (code "83") (name "Net-(U3-RS)") (class "Default")
      (node (ref "R18") (pin "1") (pinfunction "1_1") (pintype "passive"))
      (node (ref "U3") (pin "8") (pinfunction "RS_8") (pintype "passive"))
    )
    (net (code "84") (name "Net-(U3-VREF)") (class "Default")
      (node (ref "R16") (pin "1") (pinfunction "1_1") (pintype "passive"))
      (node (ref "U3") (pin "5") (pinfunction "VREF_5") (pintype "output"))
    )
    (net (code "85") (name "Net-(U4-OSC1{slash}CLKI)") (class "Default")
      (node (ref "C17") (pin "1") (pinfunction "1_1") (pintype "passive"))
      (node (ref "U4") (pin "39") (pinfunction "OSC1/CLKI_39") (pintype "passive"))
      (node (ref "Y1") (pin "2") (pinfunction "OSC2_2") (pintype "passive"))
    )
    (net (code "86") (name "Net-(U4-OSC2{slash}CLKO{slash}RC15)") (class "Default")
      (node (ref "C18") (pin "1") (pinfunction "1_1") (pintype "passive"))
      (node (ref "U4") (pin "40") (pinfunction "OSC2/CLKO/RC15_40") (pintype "passive"))
      (node (ref "Y1") (pin "1") (pinfunction "OSC1_1") (pintype "passive"))
    )
    (net (code "87") (name "Net-(U4-SCL{slash}RG2)") (class "Default")
      (node (ref "R30") (pin "2") (pinfunction "2_2") (pintype "passive"))
      (node (ref "U4") (pin "37") (pinfunction "SCL/RG2_37") (pintype "passive"))
    )
    (net (code "88") (name "Net-(U4-~{SS2}{slash}CN11{slash}RG9)") (class "Default")
      (node (ref "R33") (pin "2") (pinfunction "2_2") (pintype "passive"))
      (node (ref "U4") (pin "8") (pinfunction "~{SS2}/CN11/RG9_8") (pintype "passive"))
    )
    (net (code "89") (name "unconnected-(U4-COFS{slash}RG15-Pad1)") (class "Default")
      (node (ref "U4") (pin "1") (pinfunction "COFS/RG15_1") (pintype "passive"))
    )
    (net (code "90") (name "unconnected-(U4-CSCK{slash}RG14-Pad62)") (class "Default")
      (node (ref "U4") (pin "62") (pinfunction "CSCK/RG14_62") (pintype "passive"))
    )
    (net (code "91") (name "unconnected-(U4-CSDI{slash}RG12-Pad63)") (class "Default")
      (node (ref "U4") (pin "63") (pinfunction "CSDI/RG12_63") (pintype "passive"))
    )
    (net (code "92") (name "unconnected-(U4-CSDO{slash}RG13-Pad64)") (class "Default")
      (node (ref "U4") (pin "64") (pinfunction "CSDO/RG13_64") (pintype "passive"))
    )
    (net (code "93") (name "unconnected-(U4-EMUC3{slash}SCK1{slash}INT0{slash}RF6-Pad35)") (class "Default")
      (node (ref "U4") (pin "35") (pinfunction "EMUC3/SCK1/INT0/RF6_35") (pintype "passive"))
    )
    (net (code "94") (name "unconnected-(U4-SCK2{slash}CN8{slash}RG6-Pad4)") (class "Default")
      (node (ref "U4") (pin "4") (pinfunction "SCK2/CN8/RG6_4") (pintype "passive"))
    )
    (net (code "95") (name "unconnected-(U4-SDA{slash}RG3-Pad36)") (class "Default")
      (node (ref "U4") (pin "36") (pinfunction "SDA/RG3_36") (pintype "passive"))
    )
    (net (code "96") (name "unconnected-(U4-SDI2{slash}CN9{slash}RG7-Pad5)") (class "Default")
      (node (ref "U4") (pin "5") (pinfunction "SDI2/CN9/RG7_5") (pintype "passive"))
    )
    (net (code "97") (name "unconnected-(U4-SDO2{slash}CN10{slash}RG8-Pad6)") (class "Default")
      (node (ref "U4") (pin "6") (pinfunction "SDO2/CN10/RG8_6") (pintype "passive"))
    )
    (net (code "98") (name "unconnected-(U4-T2CK{slash}RC1-Pad2)") (class "Default")
      (node (ref "U4") (pin "2") (pinfunction "T2CK/RC1_2") (pintype "passive"))
    )
    (net (code "99") (name "unconnected-(U4-T3CK{slash}RC2-Pad3)") (class "Default")
      (node (ref "U4") (pin "3") (pinfunction "T3CK/RC2_3") (pintype "passive"))
    )
  )
)
